# granular_synthesizer_v1.net
KiCad netlist of a schematic drawn in EAGLE
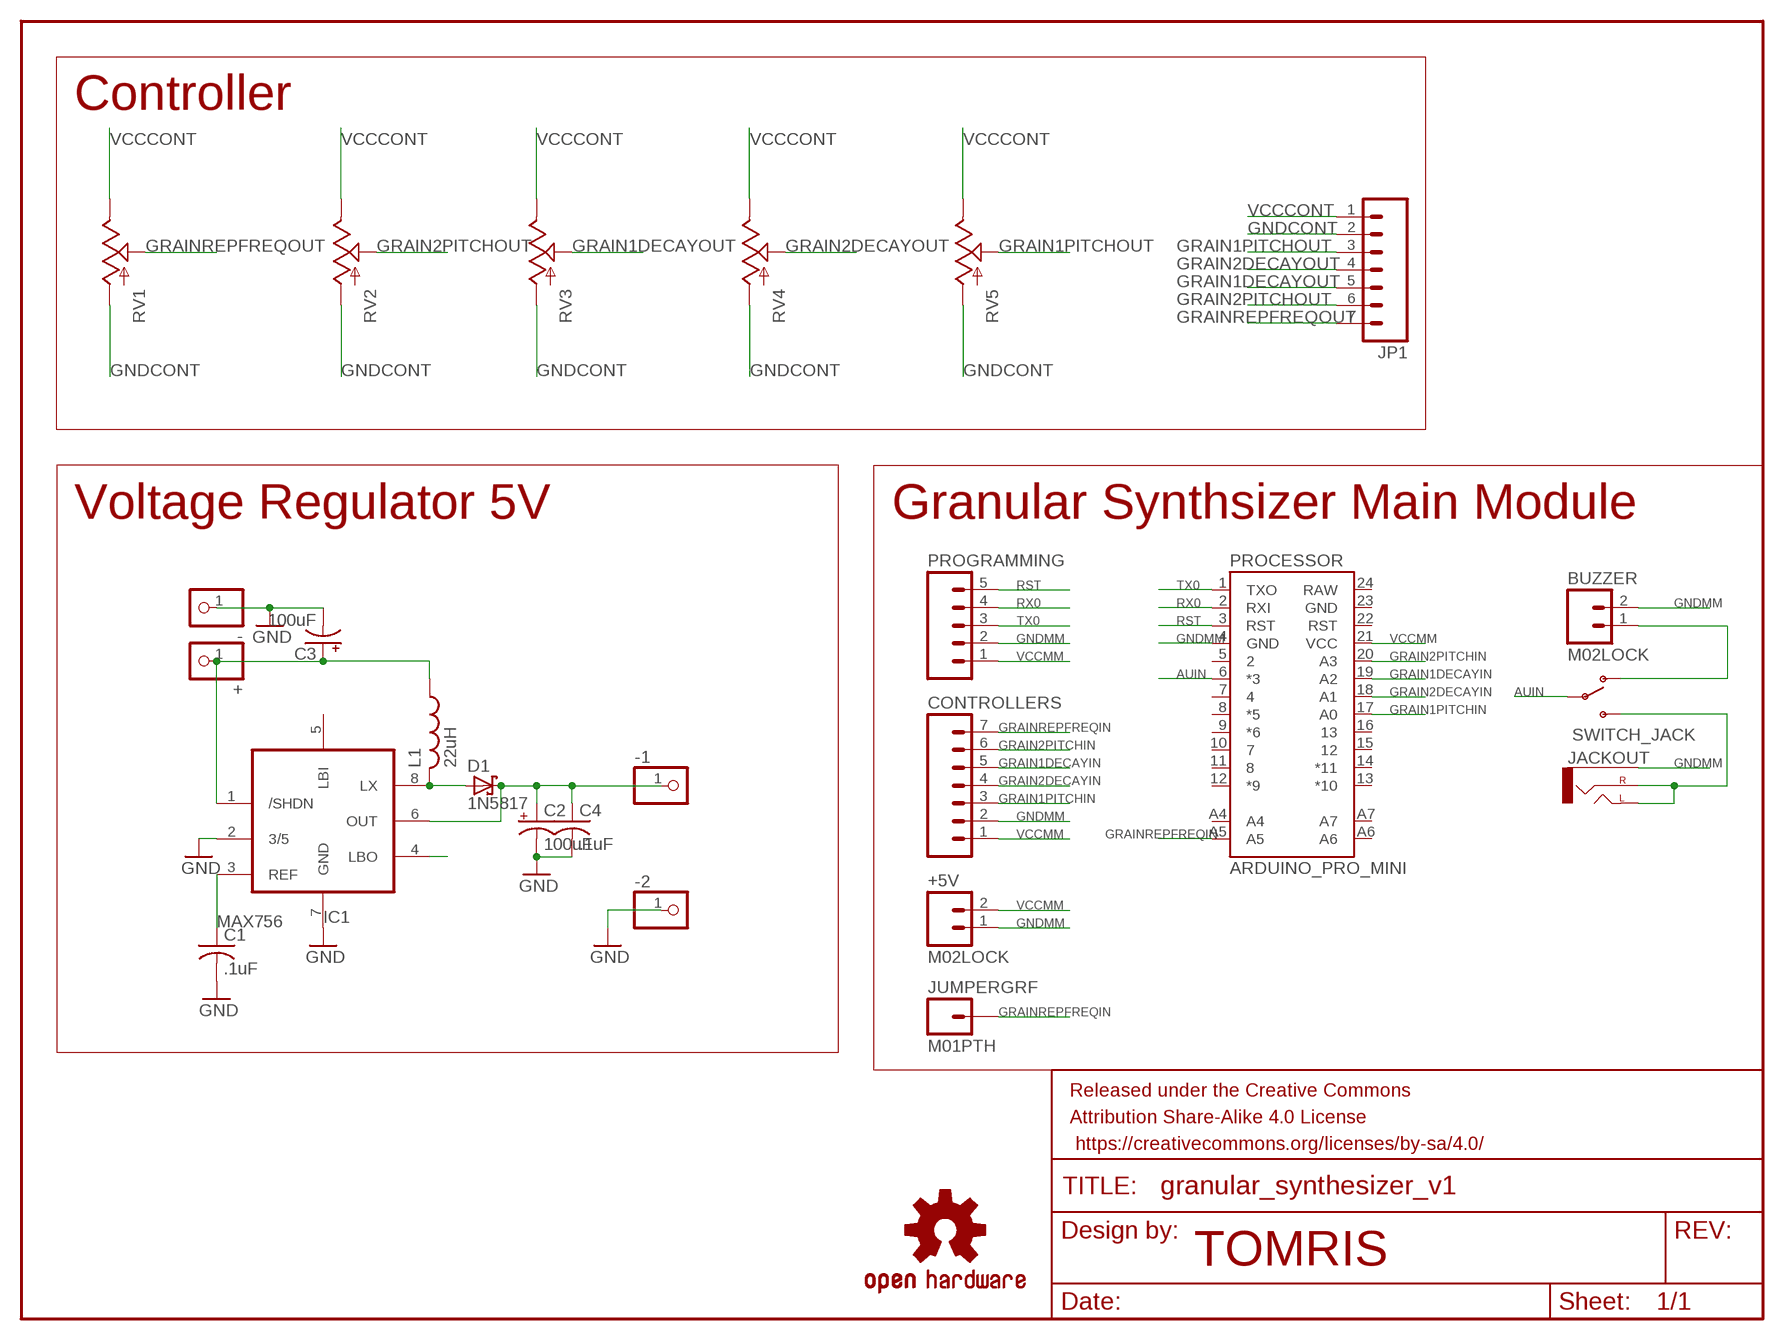
[diagram p0: schematic, sheet 1]

(export (version "E")
  (design (tool "Eeschema 10.0.6"))
  (components
    (comp (ref "+")
      (value "PINHD-1X1")
      (footprint "eagle-import:1X01")
      (libsource (lib "eagle-import") (part "PINHD-1X1"))
    )
    (comp (ref "+5V")
      (value "M02LOCK")
      (footprint "eagle-import:1X02_LOCK")
      (libsource (lib "eagle-import") (part "M02LOCK"))
    )
    (comp (ref "-")
      (value "PINHD-1X1")
      (footprint "eagle-import:1X01")
      (libsource (lib "eagle-import") (part "PINHD-1X1"))
    )
    (comp (ref "-1")
      (value "PINHD-1X1")
      (footprint "eagle-import:1X01")
      (libsource (lib "eagle-import") (part "PINHD-1X1"))
    )
    (comp (ref "-2")
      (value "PINHD-1X1")
      (footprint "eagle-import:1X01")
      (libsource (lib "eagle-import") (part "PINHD-1X1"))
    )
    (comp (ref "BUZZER")
      (value "M02LOCK")
      (footprint "eagle-import:1X02_LOCK")
      (libsource (lib "eagle-import") (part "M02LOCK"))
    )
    (comp (ref "C1")
      (value ".1uF")
      (footprint "eagle-import:C025-024X044")
      (libsource (lib "eagle-import") (part "C-US025-024X044"))
    )
    (comp (ref "C2")
      (value "100uF")
      (footprint "eagle-import:E2,5-5")
      (libsource (lib "eagle-import") (part "CPOL-USE2.5-5"))
    )
    (comp (ref "C3")
      (value "100uF")
      (footprint "eagle-import:E2,5-5")
      (libsource (lib "eagle-import") (part "CPOL-USE2.5-5"))
    )
    (comp (ref "C4")
      (value ".1uF")
      (footprint "eagle-import:C025-024X044")
      (libsource (lib "eagle-import") (part "C-US025-024X044"))
    )
    (comp (ref "CONTROLLERS")
      (value "M07")
      (footprint "eagle-import:1X07")
      (libsource (lib "eagle-import") (part "M07"))
    )
    (comp (ref "D1")
      (value "1N5817")
      (footprint "eagle-import:DO41-10")
      (libsource (lib "eagle-import") (part "SCHOTTKY-DIODEDO41"))
    )
    (comp (ref "FRAME1")
      (value "FRAME-LETTER")
      (footprint "eagle-import:CREATIVE_COMMONS")
      (libsource (lib "eagle-import") (part "FRAME-LETTER"))
    )
    (comp (ref "IC1")
      (value "MAX756")
      (footprint "eagle-import:DIL08")
      (libsource (lib "eagle-import") (part "MAX756CPA"))
    )
    (comp (ref "JACKOUT")
      (value "AUDIO-JACK2.5MM")
      (footprint "eagle-import:STEREOJACK2.5MM_STEREOJACK2.5MM")
      (libsource (lib "eagle-import") (part "AUDIO-JACK2.5MM"))
    )
    (comp (ref "JP1")
      (value "M07")
      (footprint "eagle-import:1X07")
      (libsource (lib "eagle-import") (part "M07"))
    )
    (comp (ref "JUMPERGRF")
      (value "M01PTH")
      (footprint "eagle-import:1X01")
      (libsource (lib "eagle-import") (part "M01PTH"))
    )
    (comp (ref "L1")
      (value "22uH")
      (footprint "eagle-import:2747")
      (libsource (lib "eagle-import") (part "L2474/10"))
    )
    (comp (ref "LOGO1")
      (value "OSHW-LOGOM")
      (footprint "eagle-import:OSHW-LOGO-M")
      (libsource (lib "eagle-import") (part "OSHW-LOGOM"))
    )
    (comp (ref "LOGO2")
      (value "OSHW-LOGOM")
      (footprint "eagle-import:OSHW-LOGO-M")
      (libsource (lib "eagle-import") (part "OSHW-LOGOM"))
    )
    (comp (ref "LOGO3")
      (value "OSHW-LOGOM")
      (footprint "eagle-import:OSHW-LOGO-M")
      (libsource (lib "eagle-import") (part "OSHW-LOGOM"))
    )
    (comp (ref "PROCESSOR")
      (value "ARDUINO_PRO_MINI")
      (footprint "eagle-import:ARDUINO_PRO_MINI")
      (libsource (lib "eagle-import") (part "ARDUINO_PRO_MINI"))
    )
    (comp (ref "PROGRAMMING")
      (value "M05LOCK")
      (footprint "eagle-import:1X05_LOCK")
      (libsource (lib "eagle-import") (part "M05LOCK"))
    )
    (comp (ref "RV1")
      (value "POTMAM")
      (footprint "eagle-import:POT_MAMMOTH")
      (libsource (lib "eagle-import") (part "POTMAM"))
    )
    (comp (ref "RV2")
      (value "POTMAM")
      (footprint "eagle-import:POT_MAMMOTH")
      (libsource (lib "eagle-import") (part "POTMAM"))
    )
    (comp (ref "RV3")
      (value "POTMAM")
      (footprint "eagle-import:POT_MAMMOTH")
      (libsource (lib "eagle-import") (part "POTMAM"))
    )
    (comp (ref "RV4")
      (value "POTMAM")
      (footprint "eagle-import:POT_MAMMOTH")
      (libsource (lib "eagle-import") (part "POTMAM"))
    )
    (comp (ref "RV5")
      (value "POTMAM")
      (footprint "eagle-import:POT_MAMMOTH")
      (libsource (lib "eagle-import") (part "POTMAM"))
    )
    (comp (ref "SWITCH_JACK")
      (value "SWITCH-SPDTPTH")
      (footprint "eagle-import:SWITCH-SPDT")
      (libsource (lib "eagle-import") (part "SWITCH-SPDTPTH"))
    )
  )
  (nets
    (net (code "1") (name "/AUIN") (class "Default")
      (node (ref "PROCESSOR") (pin "6") (pinfunction "*3_6") (pintype "bidirectional"))
      (node (ref "SWITCH_JACK") (pin "2") (pinfunction "P_2") (pintype "passive"))
    )
    (net (code "2") (name "/GNDCONT") (class "Default")
      (node (ref "JP1") (pin "2") (pinfunction "2_2") (pintype "passive"))
      (node (ref "RV1") (pin "P$2") (pinfunction "A_P$2") (pintype "passive"))
      (node (ref "RV2") (pin "P$2") (pinfunction "A_P$2") (pintype "passive"))
      (node (ref "RV3") (pin "P$2") (pinfunction "A_P$2") (pintype "passive"))
      (node (ref "RV4") (pin "P$2") (pinfunction "A_P$2") (pintype "passive"))
      (node (ref "RV5") (pin "P$2") (pinfunction "A_P$2") (pintype "passive"))
    )
    (net (code "3") (name "/GNDMM") (class "Default")
      (node (ref "+5V") (pin "1") (pinfunction "1_1") (pintype "passive"))
      (node (ref "BUZZER") (pin "2") (pinfunction "2_2") (pintype "passive"))
      (node (ref "CONTROLLERS") (pin "2") (pinfunction "2_2") (pintype "passive"))
      (node (ref "JACKOUT") (pin "RING1") (pinfunction "SLEEVE_RING1") (pintype "bidirectional"))
      (node (ref "PROCESSOR") (pin "4") (pinfunction "GND_4") (pintype "bidirectional"))
      (node (ref "PROGRAMMING") (pin "2") (pinfunction "2_2") (pintype "passive"))
    )
    (net (code "4") (name "/GRAIN1DECAYIN") (class "Default")
      (node (ref "CONTROLLERS") (pin "5") (pinfunction "5_5") (pintype "passive"))
      (node (ref "PROCESSOR") (pin "19") (pinfunction "A2_19") (pintype "bidirectional"))
    )
    (net (code "5") (name "/GRAIN1DECAYOUT") (class "Default")
      (node (ref "JP1") (pin "5") (pinfunction "5_5") (pintype "passive"))
      (node (ref "RV3") (pin "P$1") (pinfunction "S_P$1") (pintype "passive"))
    )
    (net (code "6") (name "/GRAIN1PITCHIN") (class "Default")
      (node (ref "CONTROLLERS") (pin "3") (pinfunction "3_3") (pintype "passive"))
      (node (ref "PROCESSOR") (pin "17") (pinfunction "A0_17") (pintype "bidirectional"))
    )
    (net (code "7") (name "/GRAIN1PITCHOUT") (class "Default")
      (node (ref "JP1") (pin "3") (pinfunction "3_3") (pintype "passive"))
      (node (ref "RV5") (pin "P$1") (pinfunction "S_P$1") (pintype "passive"))
    )
    (net (code "8") (name "/GRAIN2DECAYIN") (class "Default")
      (node (ref "CONTROLLERS") (pin "4") (pinfunction "4_4") (pintype "passive"))
      (node (ref "PROCESSOR") (pin "18") (pinfunction "A1_18") (pintype "bidirectional"))
    )
    (net (code "9") (name "/GRAIN2DECAYOUT") (class "Default")
      (node (ref "JP1") (pin "4") (pinfunction "4_4") (pintype "passive"))
      (node (ref "RV4") (pin "P$1") (pinfunction "S_P$1") (pintype "passive"))
    )
    (net (code "10") (name "/GRAIN2PITCHIN") (class "Default")
      (node (ref "CONTROLLERS") (pin "6") (pinfunction "6_6") (pintype "passive"))
      (node (ref "PROCESSOR") (pin "20") (pinfunction "A3_20") (pintype "bidirectional"))
    )
    (net (code "11") (name "/GRAIN2PITCHOUT") (class "Default")
      (node (ref "JP1") (pin "6") (pinfunction "6_6") (pintype "passive"))
      (node (ref "RV2") (pin "P$1") (pinfunction "S_P$1") (pintype "passive"))
    )
    (net (code "12") (name "/GRAINREPFREQIN") (class "Default")
      (node (ref "CONTROLLERS") (pin "7") (pinfunction "7_7") (pintype "passive"))
      (node (ref "JUMPERGRF") (pin "1") (pinfunction "1_1") (pintype "passive"))
      (node (ref "PROCESSOR") (pin "A5") (pinfunction "A5_A5") (pintype "bidirectional"))
    )
    (net (code "13") (name "/GRAINREPFREQOUT") (class "Default")
      (node (ref "JP1") (pin "7") (pinfunction "7_7") (pintype "passive"))
      (node (ref "RV1") (pin "P$1") (pinfunction "S_P$1") (pintype "passive"))
    )
    (net (code "14") (name "/RST") (class "Default")
      (node (ref "PROCESSOR") (pin "3") (pinfunction "RST_3") (pintype "bidirectional"))
      (node (ref "PROGRAMMING") (pin "5") (pinfunction "5_5") (pintype "passive"))
    )
    (net (code "15") (name "/RX0") (class "Default")
      (node (ref "PROCESSOR") (pin "2") (pinfunction "RXI_2") (pintype "bidirectional"))
      (node (ref "PROGRAMMING") (pin "4") (pinfunction "4_4") (pintype "passive"))
    )
    (net (code "16") (name "/TX0") (class "Default")
      (node (ref "PROCESSOR") (pin "1") (pinfunction "TXO_1") (pintype "bidirectional"))
      (node (ref "PROGRAMMING") (pin "3") (pinfunction "3_3") (pintype "passive"))
    )
    (net (code "17") (name "/VCCCONT") (class "Default")
      (node (ref "JP1") (pin "1") (pinfunction "1_1") (pintype "passive"))
      (node (ref "RV1") (pin "P$3") (pinfunction "E_P$3") (pintype "passive"))
      (node (ref "RV2") (pin "P$3") (pinfunction "E_P$3") (pintype "passive"))
      (node (ref "RV3") (pin "P$3") (pinfunction "E_P$3") (pintype "passive"))
      (node (ref "RV4") (pin "P$3") (pinfunction "E_P$3") (pintype "passive"))
      (node (ref "RV5") (pin "P$3") (pinfunction "E_P$3") (pintype "passive"))
    )
    (net (code "18") (name "/VCCMM") (class "Default")
      (node (ref "+5V") (pin "2") (pinfunction "2_2") (pintype "passive"))
      (node (ref "CONTROLLERS") (pin "1") (pinfunction "1_1") (pintype "passive"))
      (node (ref "PROCESSOR") (pin "21") (pinfunction "VCC_21") (pintype "bidirectional"))
      (node (ref "PROGRAMMING") (pin "1") (pinfunction "1_1") (pintype "passive"))
    )
    (net (code "19") (name "GND") (class "Default")
      (node (ref "-") (pin "1") (pinfunction "1_1") (pintype "passive"))
      (node (ref "-2") (pin "1") (pinfunction "1_1") (pintype "passive"))
      (node (ref "C1") (pin "2") (pinfunction "2_2") (pintype "passive"))
      (node (ref "C2") (pin "-") (pinfunction "-_-") (pintype "passive"))
      (node (ref "C3") (pin "-") (pinfunction "-_-") (pintype "passive"))
      (node (ref "C4") (pin "2") (pinfunction "2_2") (pintype "passive"))
      (node (ref "IC1") (pin "2") (pinfunction "3/5_2") (pintype "bidirectional"))
      (node (ref "IC1") (pin "7") (pinfunction "GND_7") (pintype "power_in"))
    )
    (net (code "20") (name "Net-(IC1-LX)") (class "Default")
      (node (ref "D1") (pin "A") (pinfunction "A_A") (pintype "passive"))
      (node (ref "IC1") (pin "8") (pinfunction "LX_8") (pintype "output"))
      (node (ref "L1") (pin "P$2") (pinfunction "2_P$2") (pintype "passive"))
    )
    (net (code "21") (name "Net-(IC1-OUT)") (class "Default")
      (node (ref "-1") (pin "1") (pinfunction "1_1") (pintype "passive"))
      (node (ref "C2") (pin "+") (pinfunction "+_+") (pintype "passive"))
      (node (ref "C4") (pin "1") (pinfunction "1_1") (pintype "passive"))
      (node (ref "D1") (pin "C") (pinfunction "C_C") (pintype "passive"))
      (node (ref "IC1") (pin "6") (pinfunction "OUT_6") (pintype "output"))
    )
    (net (code "22") (name "Net-(IC1-REF)") (class "Default")
      (node (ref "C1") (pin "1") (pinfunction "1_1") (pintype "passive"))
      (node (ref "IC1") (pin "3") (pinfunction "REF_3") (pintype "passive"))
    )
    (net (code "23") (name "Net-(IC1-{slash}SHDN)") (class "Default")
      (node (ref "+") (pin "1") (pinfunction "1_1") (pintype "passive"))
      (node (ref "C3") (pin "+") (pinfunction "+_+") (pintype "passive"))
      (node (ref "IC1") (pin "1") (pinfunction "/SHDN_1") (pintype "input"))
      (node (ref "L1") (pin "P$1") (pinfunction "1_P$1") (pintype "passive"))
    )
    (net (code "24") (name "Net-(JACKOUT-LEFT)") (class "Default")
      (node (ref "JACKOUT") (pin "SHIELD") (pinfunction "LEFT_SHIELD") (pintype "bidirectional"))
      (node (ref "JACKOUT") (pin "TIP") (pinfunction "RIGHT_TIP") (pintype "bidirectional"))
      (node (ref "SWITCH_JACK") (pin "3") (pinfunction "S_3") (pintype "passive"))
    )
    (net (code "25") (name "Net-(SWITCH_JACK-O)") (class "Default")
      (node (ref "BUZZER") (pin "1") (pinfunction "1_1") (pintype "passive"))
      (node (ref "SWITCH_JACK") (pin "1") (pinfunction "O_1") (pintype "passive"))
    )
    (net (code "26") (name "unconnected-(IC1-LBI-Pad5)") (class "Default")
      (node (ref "IC1") (pin "5") (pinfunction "LBI_5") (pintype "input"))
    )
    (net (code "27") (name "unconnected-(IC1-LBO-Pad4)") (class "Default")
      (node (ref "IC1") (pin "4") (pinfunction "LBO_4") (pintype "input"))
    )
    (net (code "28") (name "unconnected-(PROCESSOR-*5-Pad8)") (class "Default")
      (node (ref "PROCESSOR") (pin "8") (pinfunction "*5_8") (pintype "bidirectional"))
    )
    (net (code "29") (name "unconnected-(PROCESSOR-*6-Pad9)") (class "Default")
      (node (ref "PROCESSOR") (pin "9") (pinfunction "*6_9") (pintype "bidirectional"))
    )
    (net (code "30") (name "unconnected-(PROCESSOR-*9-Pad12)") (class "Default")
      (node (ref "PROCESSOR") (pin "12") (pinfunction "*9_12") (pintype "bidirectional"))
    )
    (net (code "31") (name "unconnected-(PROCESSOR-*10-Pad13)") (class "Default")
      (node (ref "PROCESSOR") (pin "13") (pinfunction "*10_13") (pintype "bidirectional"))
    )
    (net (code "32") (name "unconnected-(PROCESSOR-*11-Pad14)") (class "Default")
      (node (ref "PROCESSOR") (pin "14") (pinfunction "*11_14") (pintype "bidirectional"))
    )
    (net (code "33") (name "unconnected-(PROCESSOR-2-Pad5)") (class "Default")
      (node (ref "PROCESSOR") (pin "5") (pinfunction "2_5") (pintype "bidirectional"))
    )
    (net (code "34") (name "unconnected-(PROCESSOR-4-Pad7)") (class "Default")
      (node (ref "PROCESSOR") (pin "7") (pinfunction "4_7") (pintype "bidirectional"))
    )
    (net (code "35") (name "unconnected-(PROCESSOR-7-Pad10)") (class "Default")
      (node (ref "PROCESSOR") (pin "10") (pinfunction "7_10") (pintype "bidirectional"))
    )
    (net (code "36") (name "unconnected-(PROCESSOR-8-Pad11)") (class "Default")
      (node (ref "PROCESSOR") (pin "11") (pinfunction "8_11") (pintype "bidirectional"))
    )
    (net (code "37") (name "unconnected-(PROCESSOR-12-Pad15)") (class "Default")
      (node (ref "PROCESSOR") (pin "15") (pinfunction "12_15") (pintype "bidirectional"))
    )
    (net (code "38") (name "unconnected-(PROCESSOR-13-Pad16)") (class "Default")
      (node (ref "PROCESSOR") (pin "16") (pinfunction "13_16") (pintype "bidirectional"))
    )
    (net (code "39") (name "unconnected-(PROCESSOR-GND-Pad23)") (class "Default")
      (node (ref "PROCESSOR") (pin "23") (pinfunction "GND_23") (pintype "bidirectional"))
    )
    (net (code "40") (name "unconnected-(PROCESSOR-PadA4)") (class "Default")
      (node (ref "PROCESSOR") (pin "A4") (pinfunction "A4_A4") (pintype "bidirectional"))
    )
    (net (code "41") (name "unconnected-(PROCESSOR-PadA6)") (class "Default")
      (node (ref "PROCESSOR") (pin "A6") (pinfunction "A6_A6") (pintype "bidirectional"))
    )
    (net (code "42") (name "unconnected-(PROCESSOR-PadA7)") (class "Default")
      (node (ref "PROCESSOR") (pin "A7") (pinfunction "A7_A7") (pintype "bidirectional"))
    )
    (net (code "43") (name "unconnected-(PROCESSOR-RAW-Pad24)") (class "Default")
      (node (ref "PROCESSOR") (pin "24") (pinfunction "RAW_24") (pintype "bidirectional"))
    )
    (net (code "44") (name "unconnected-(PROCESSOR-RST-Pad22)") (class "Default")
      (node (ref "PROCESSOR") (pin "22") (pinfunction "RST_22") (pintype "bidirectional"))
    )
  )
)
